# USBIOV2.net
KiCad netlist of a schematic drawn in EAGLE
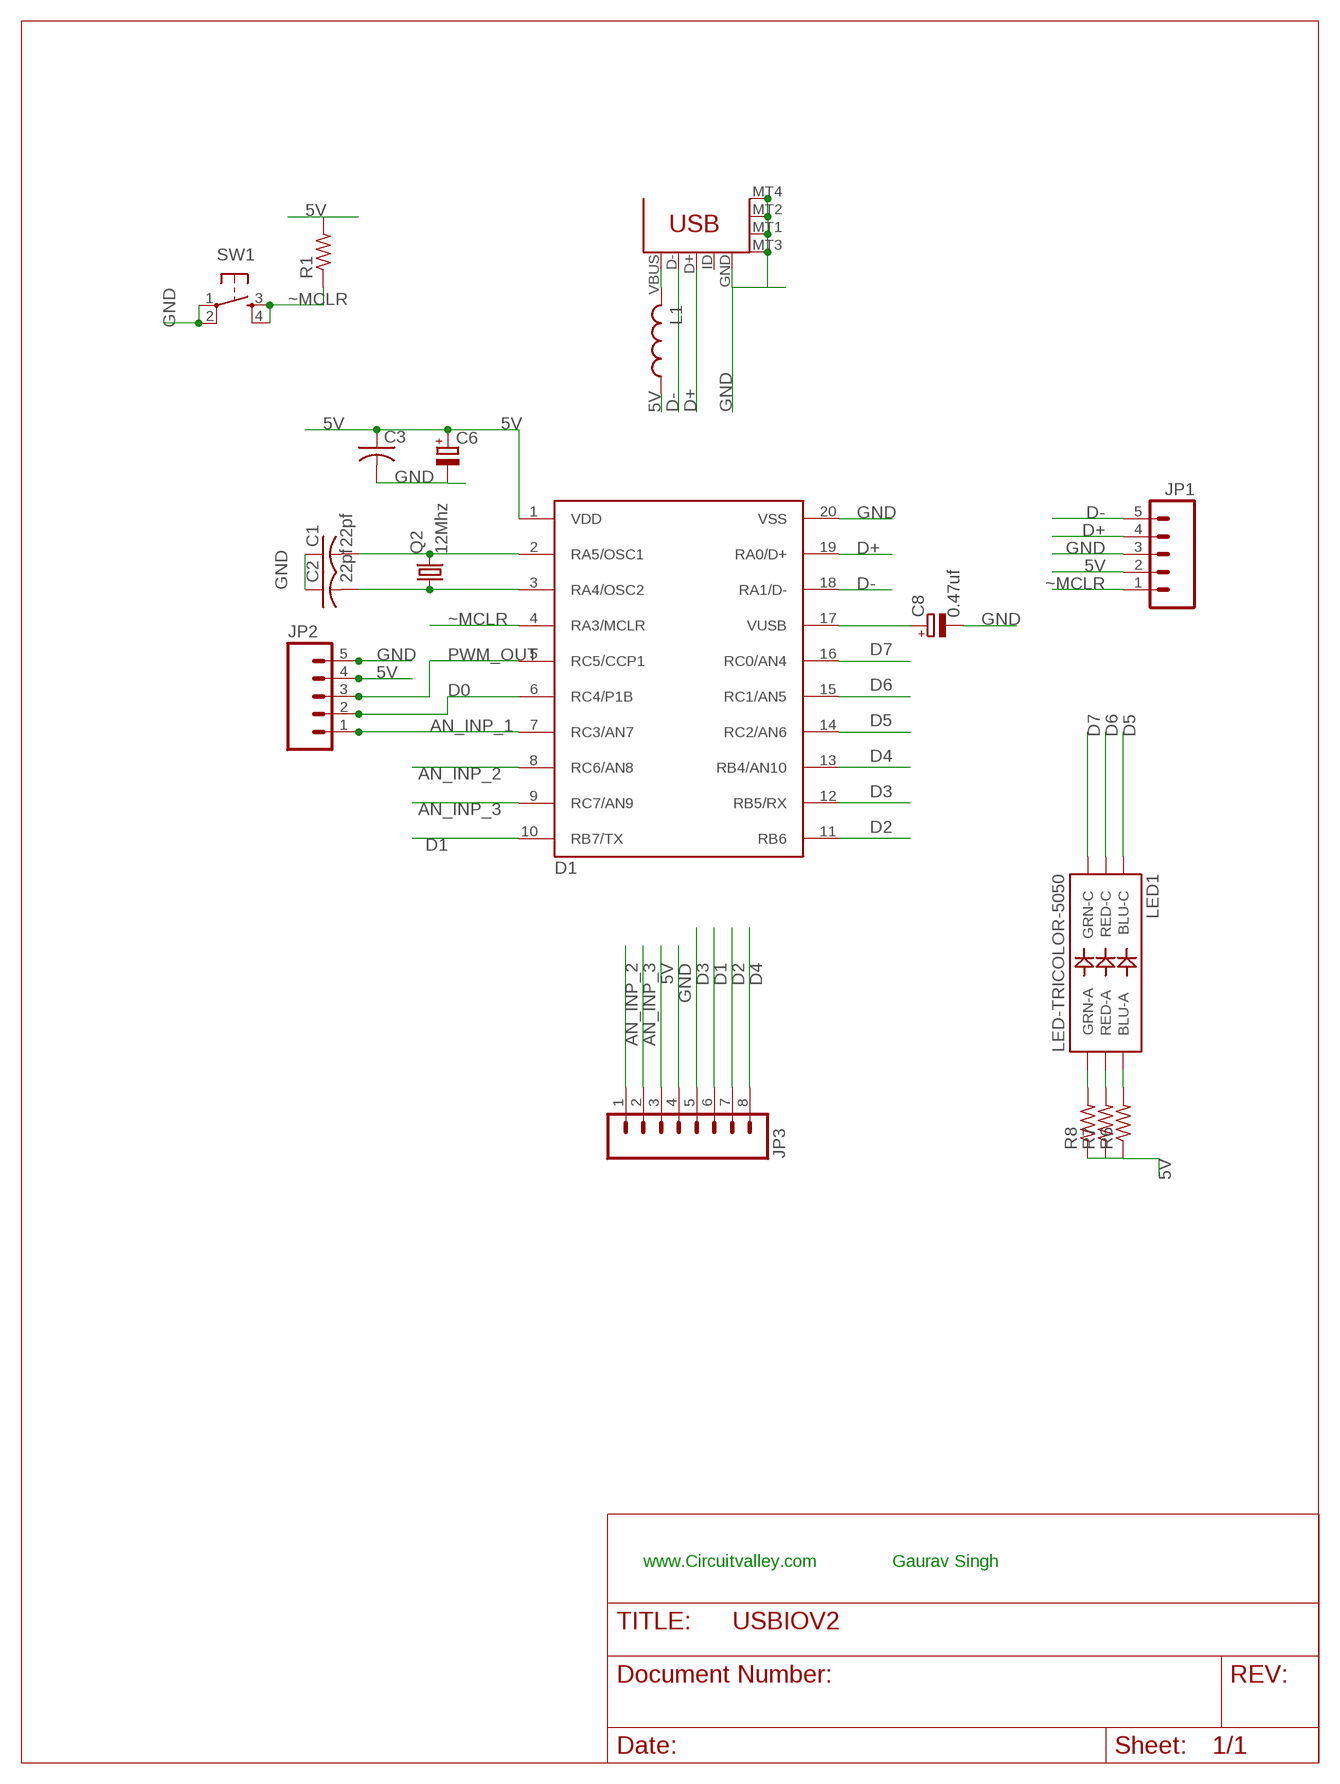
[diagram p0: schematic, sheet 1]

(export (version "E")
  (design (tool "Eeschema 10.0.6"))
  (components
    (comp (ref "C1")
      (value "22pf")
      (footprint "eagle-import:C0805")
      (libsource (lib "eagle-import") (part "C-USC0805"))
    )
    (comp (ref "C2")
      (value "22pf")
      (footprint "eagle-import:C0805")
      (libsource (lib "eagle-import") (part "C-USC0805"))
    )
    (comp (ref "C3")
      (value "C-USC0805")
      (footprint "eagle-import:C0805")
      (libsource (lib "eagle-import") (part "C-USC0805"))
    )
    (comp (ref "C6")
      (value "CAP_POLSMC_B")
      (footprint "eagle-import:SMC_B")
      (libsource (lib "eagle-import") (part "CAP_POLSMC_B"))
    )
    (comp (ref "C8")
      (value "0.47uf")
      (footprint "eagle-import:SMC_B")
      (libsource (lib "eagle-import") (part "CAP_POLSMC_B"))
    )
    (comp (ref "D1")
      (value "PIC18F14K50D")
      (footprint "eagle-import:SSOP20")
      (libsource (lib "eagle-import") (part "PIC18F14K50D"))
    )
    (comp (ref "JP1")
      (value "M05PTH")
      (footprint "eagle-import:1X05")
      (libsource (lib "eagle-import") (part "M05PTH"))
    )
    (comp (ref "JP2")
      (value "M05PTH")
      (footprint "eagle-import:1X05")
      (libsource (lib "eagle-import") (part "M05PTH"))
    )
    (comp (ref "JP3")
      (value "M081X08")
      (footprint "eagle-import:1X08")
      (libsource (lib "eagle-import") (part "M081X08"))
    )
    (comp (ref "L1")
      (value "L-USL3225M")
      (footprint "eagle-import:L3225M")
      (libsource (lib "eagle-import") (part "L-USL3225M"))
    )
    (comp (ref "LED1")
      (value "LED-TRICOLOR-5050")
      (footprint "eagle-import:LED-TRICOLOR-5050")
      (libsource (lib "eagle-import") (part "LED-TRICOLOR-5050"))
    )
    (comp (ref "Q2")
      (value "12Mhz")
      (footprint "eagle-import:HC49UP")
      (libsource (lib "eagle-import") (part "CRYSTALHC49UP"))
    )
    (comp (ref "R1")
      (value "R-US_M0805")
      (footprint "eagle-import:M0805")
      (libsource (lib "eagle-import") (part "R-US_M0805"))
    )
    (comp (ref "R6")
      (value "R-US_M0805")
      (footprint "eagle-import:M0805")
      (libsource (lib "eagle-import") (part "R-US_M0805"))
    )
    (comp (ref "R7")
      (value "R-US_M0805")
      (footprint "eagle-import:M0805")
      (libsource (lib "eagle-import") (part "R-US_M0805"))
    )
    (comp (ref "R8")
      (value "R-US_M0805")
      (footprint "eagle-import:M0805")
      (libsource (lib "eagle-import") (part "R-US_M0805"))
    )
    (comp (ref "SW1")
      (value "SW-SMD-SMALL")
      (footprint "eagle-import:TACT_SWITCH_SMALL")
      (libsource (lib "eagle-import") (part "SW-SMD-SMALL"))
    )
    (comp (ref "U$1")
      (value "USB-MICROB-HW-MC-5F")
      (footprint "eagle-import:USB-MICROB-HW-MC-5F-01")
      (libsource (lib "eagle-import") (part "USB-MICROB-HW-MC-5F"))
    )
  )
  (nets
    (net (code "1") (name "/5V") (class "Default")
      (node (ref "C3") (pin "1") (pinfunction "1_1") (pintype "passive"))
      (node (ref "C6") (pin "+") (pinfunction "+_+") (pintype "passive"))
      (node (ref "D1") (pin "1") (pinfunction "VDD_1") (pintype "bidirectional"))
      (node (ref "JP1") (pin "2") (pinfunction "2_2") (pintype "passive"))
      (node (ref "JP2") (pin "4") (pinfunction "4_4") (pintype "passive"))
      (node (ref "JP3") (pin "3") (pinfunction "3_3") (pintype "passive"))
      (node (ref "L1") (pin "1") (pinfunction "1_1") (pintype "passive"))
      (node (ref "R1") (pin "2") (pinfunction "2_2") (pintype "passive"))
      (node (ref "R6") (pin "1") (pinfunction "1_1") (pintype "passive"))
      (node (ref "R7") (pin "1") (pinfunction "1_1") (pintype "passive"))
      (node (ref "R8") (pin "1") (pinfunction "1_1") (pintype "passive"))
    )
    (net (code "2") (name "/AN_INP_1") (class "Default")
      (node (ref "D1") (pin "7") (pinfunction "RC3/AN7_7") (pintype "bidirectional"))
      (node (ref "JP2") (pin "1") (pinfunction "1_1") (pintype "passive"))
    )
    (net (code "3") (name "/AN_INP_2") (class "Default")
      (node (ref "D1") (pin "8") (pinfunction "RC6/AN8_8") (pintype "bidirectional"))
      (node (ref "JP3") (pin "1") (pinfunction "1_1") (pintype "passive"))
    )
    (net (code "4") (name "/AN_INP_3") (class "Default")
      (node (ref "D1") (pin "9") (pinfunction "RC7/AN9_9") (pintype "bidirectional"))
      (node (ref "JP3") (pin "2") (pinfunction "2_2") (pintype "passive"))
    )
    (net (code "5") (name "/D+") (class "Default")
      (node (ref "D1") (pin "19") (pinfunction "RA0/D+_19") (pintype "bidirectional"))
      (node (ref "JP1") (pin "4") (pinfunction "4_4") (pintype "passive"))
      (node (ref "U$1") (pin "D+") (pinfunction "D+_D+") (pintype "bidirectional"))
    )
    (net (code "6") (name "/D-") (class "Default")
      (node (ref "D1") (pin "18") (pinfunction "RA1/D-_18") (pintype "bidirectional"))
      (node (ref "JP1") (pin "5") (pinfunction "5_5") (pintype "passive"))
      (node (ref "U$1") (pin "D-") (pinfunction "D-_D-") (pintype "bidirectional"))
    )
    (net (code "7") (name "/D0") (class "Default")
      (node (ref "D1") (pin "6") (pinfunction "RC4/P1B_6") (pintype "bidirectional"))
      (node (ref "JP2") (pin "2") (pinfunction "2_2") (pintype "passive"))
    )
    (net (code "8") (name "/D1") (class "Default")
      (node (ref "D1") (pin "10") (pinfunction "RB7/TX_10") (pintype "bidirectional"))
      (node (ref "JP3") (pin "6") (pinfunction "6_6") (pintype "passive"))
    )
    (net (code "9") (name "/D2") (class "Default")
      (node (ref "D1") (pin "11") (pinfunction "RB6_11") (pintype "bidirectional"))
      (node (ref "JP3") (pin "7") (pinfunction "7_7") (pintype "passive"))
    )
    (net (code "10") (name "/D3") (class "Default")
      (node (ref "D1") (pin "12") (pinfunction "RB5/RX_12") (pintype "bidirectional"))
      (node (ref "JP3") (pin "5") (pinfunction "5_5") (pintype "passive"))
    )
    (net (code "11") (name "/D4") (class "Default")
      (node (ref "D1") (pin "13") (pinfunction "RB4/AN10_13") (pintype "bidirectional"))
      (node (ref "JP3") (pin "8") (pinfunction "8_8") (pintype "passive"))
    )
    (net (code "12") (name "/D5") (class "Default")
      (node (ref "D1") (pin "14") (pinfunction "RC2/AN6_14") (pintype "bidirectional"))
      (node (ref "LED1") (pin "1") (pinfunction "BLU-C_1") (pintype "bidirectional"))
    )
    (net (code "13") (name "/D6") (class "Default")
      (node (ref "D1") (pin "15") (pinfunction "RC1/AN5_15") (pintype "bidirectional"))
      (node (ref "LED1") (pin "2") (pinfunction "RED-C_2") (pintype "bidirectional"))
    )
    (net (code "14") (name "/D7") (class "Default")
      (node (ref "D1") (pin "16") (pinfunction "RC0/AN4_16") (pintype "bidirectional"))
      (node (ref "LED1") (pin "3") (pinfunction "GRN-C_3") (pintype "bidirectional"))
    )
    (net (code "15") (name "/GND") (class "Default")
      (node (ref "C1") (pin "1") (pinfunction "1_1") (pintype "passive"))
      (node (ref "C2") (pin "1") (pinfunction "1_1") (pintype "passive"))
      (node (ref "C3") (pin "2") (pinfunction "2_2") (pintype "passive"))
      (node (ref "C6") (pin "-") (pinfunction "-_-") (pintype "passive"))
      (node (ref "C8") (pin "-") (pinfunction "-_-") (pintype "passive"))
      (node (ref "D1") (pin "20") (pinfunction "VSS_20") (pintype "bidirectional"))
      (node (ref "JP1") (pin "3") (pinfunction "3_3") (pintype "passive"))
      (node (ref "JP2") (pin "5") (pinfunction "5_5") (pintype "passive"))
      (node (ref "JP3") (pin "4") (pinfunction "4_4") (pintype "passive"))
      (node (ref "SW1") (pin "1") (pinfunction "1_1") (pintype "passive"))
      (node (ref "SW1") (pin "2") (pinfunction "2_2") (pintype "passive"))
      (node (ref "U$1") (pin "GND") (pinfunction "GND_GND") (pintype "bidirectional"))
      (node (ref "U$1") (pin "MT1") (pinfunction "MTN3_MT1") (pintype "bidirectional"))
      (node (ref "U$1") (pin "MT2") (pinfunction "MTN4_MT2") (pintype "bidirectional"))
      (node (ref "U$1") (pin "MT3") (pinfunction "MTN1_MT3") (pintype "bidirectional"))
      (node (ref "U$1") (pin "MT4") (pinfunction "MTN2_MT4") (pintype "bidirectional"))
    )
    (net (code "16") (name "/PWM_OUT") (class "Default")
      (node (ref "D1") (pin "5") (pinfunction "RC5/CCP1_5") (pintype "bidirectional"))
      (node (ref "JP2") (pin "3") (pinfunction "3_3") (pintype "passive"))
    )
    (net (code "17") (name "/~{MCLR}") (class "Default")
      (node (ref "D1") (pin "4") (pinfunction "RA3/MCLR_4") (pintype "bidirectional"))
      (node (ref "JP1") (pin "1") (pinfunction "1_1") (pintype "passive"))
      (node (ref "R1") (pin "1") (pinfunction "1_1") (pintype "passive"))
      (node (ref "SW1") (pin "3") (pinfunction "3_3") (pintype "passive"))
      (node (ref "SW1") (pin "4") (pinfunction "4_4") (pintype "passive"))
    )
    (net (code "18") (name "Net-(D1-RA4{slash}OSC2)") (class "Default")
      (node (ref "C2") (pin "2") (pinfunction "2_2") (pintype "passive"))
      (node (ref "D1") (pin "3") (pinfunction "RA4/OSC2_3") (pintype "bidirectional"))
      (node (ref "Q2") (pin "1") (pinfunction "1_1") (pintype "passive"))
    )
    (net (code "19") (name "Net-(D1-RA5{slash}OSC1)") (class "Default")
      (node (ref "C1") (pin "2") (pinfunction "2_2") (pintype "passive"))
      (node (ref "D1") (pin "2") (pinfunction "RA5/OSC1_2") (pintype "bidirectional"))
      (node (ref "Q2") (pin "2") (pinfunction "2_2") (pintype "passive"))
    )
    (net (code "20") (name "Net-(D1-VUSB)") (class "Default")
      (node (ref "C8") (pin "+") (pinfunction "+_+") (pintype "passive"))
      (node (ref "D1") (pin "17") (pinfunction "VUSB_17") (pintype "bidirectional"))
    )
    (net (code "21") (name "Net-(L1-Pad2)") (class "Default")
      (node (ref "L1") (pin "2") (pinfunction "2_2") (pintype "passive"))
      (node (ref "U$1") (pin "VBUS") (pinfunction "VBUS_VBUS") (pintype "bidirectional"))
    )
    (net (code "22") (name "Net-(LED1-BLU-A)") (class "Default")
      (node (ref "LED1") (pin "6") (pinfunction "BLU-A_6") (pintype "bidirectional"))
      (node (ref "R6") (pin "2") (pinfunction "2_2") (pintype "passive"))
    )
    (net (code "23") (name "Net-(LED1-GRN-A)") (class "Default")
      (node (ref "LED1") (pin "4") (pinfunction "GRN-A_4") (pintype "bidirectional"))
      (node (ref "R8") (pin "2") (pinfunction "2_2") (pintype "passive"))
    )
    (net (code "24") (name "Net-(LED1-RED-A)") (class "Default")
      (node (ref "LED1") (pin "5") (pinfunction "RED-A_5") (pintype "bidirectional"))
      (node (ref "R7") (pin "2") (pinfunction "2_2") (pintype "passive"))
    )
    (net (code "25") (name "unconnected-(U$1-PadID)") (class "Default")
      (node (ref "U$1") (pin "ID") (pinfunction "ID_ID") (pintype "bidirectional"))
    )
  )
)
